# PIC18F25k50-USB_ICSP-Board.net
KiCad netlist of a schematic drawn in EAGLE
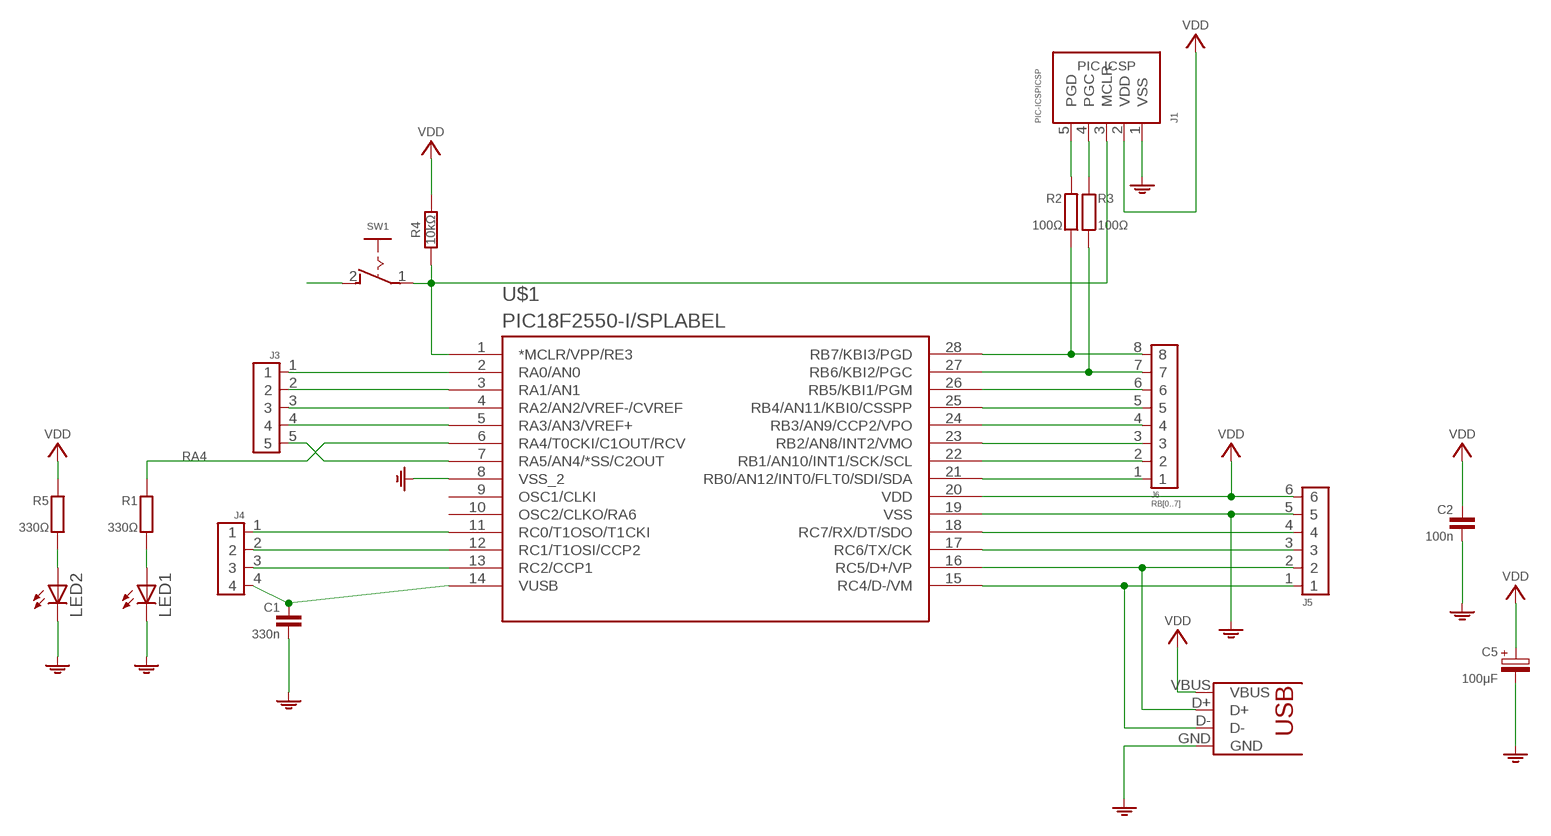
[diagram p0: schematic, sheet 1]

(export (version "E")
  (design (tool "Eeschema 10.0.6"))
  (components
    (comp (ref "C1")
      (value "330n")
      (footprint "eagle-import:C050-030X075")
      (libsource (lib "eagle-import") (part "C050-030X075"))
    )
    (comp (ref "C2")
      (value "100n")
      (footprint "eagle-import:C025-015X024")
      (libsource (lib "eagle-import") (part "C025-015X024"))
    )
    (comp (ref "C5")
      (value "100μF")
      (footprint "eagle-import:E2,5-5")
      (libsource (lib "eagle-import") (part "CPOLE2.5-5"))
    )
    (comp (ref "J1")
      (value "PIC-ICSPICSP")
      (footprint "eagle-import:PIC-ICSP")
      (libsource (lib "eagle-import") (part "PIC-ICSPICSP"))
    )
    (comp (ref "J2")
      (value "USB-PRINT")
      (footprint "eagle-import:USB-B-PRINT")
      (libsource (lib "eagle-import") (part "USB-PRINT"))
    )
    (comp (ref "J3")
      (value "RA[0..4]")
      (footprint "eagle-import:CONN-5P")
      (libsource (lib "eagle-import") (part "CONN-5P-5P"))
    )
    (comp (ref "J4")
      (value "RC[0..3]")
      (footprint "eagle-import:CONN-4P")
      (libsource (lib "eagle-import") (part "CONN-4P-4P"))
    )
    (comp (ref "J5")
      (value "PWR+SCI+USB")
      (footprint "eagle-import:CONN-6P")
      (libsource (lib "eagle-import") (part "CONN-6P"))
    )
    (comp (ref "J6")
      (value "RB[0..7]")
      (footprint "eagle-import:CONN-8P")
      (libsource (lib "eagle-import") (part "CONN-8P"))
    )
    (comp (ref "LED1")
      (value "LED5MM")
      (footprint "eagle-import:LED5MM")
      (libsource (lib "eagle-import") (part "LED5MM"))
    )
    (comp (ref "LED2")
      (value "LED5MM")
      (footprint "eagle-import:LED5MM")
      (libsource (lib "eagle-import") (part "LED5MM"))
    )
    (comp (ref "R1")
      (value "330Ω")
      (footprint "eagle-import:0204_10")
      (libsource (lib "eagle-import") (part "R0204/10"))
    )
    (comp (ref "R2")
      (value "100Ω")
      (footprint "eagle-import:0204_7-V")
      (libsource (lib "eagle-import") (part "R0204/7-V"))
    )
    (comp (ref "R3")
      (value "100Ω")
      (footprint "eagle-import:0204_7-V")
      (libsource (lib "eagle-import") (part "R0204/7-V"))
    )
    (comp (ref "R4")
      (value "10kΩ")
      (footprint "eagle-import:0204_10")
      (libsource (lib "eagle-import") (part "R-H0204/10"))
    )
    (comp (ref "R5")
      (value "330Ω")
      (footprint "eagle-import:0204_10")
      (libsource (lib "eagle-import") (part "R0204/10"))
    )
    (comp (ref "SW1")
      (value "PB-1P-1T")
      (footprint "eagle-import:PB-1P1T")
      (libsource (lib "eagle-import") (part "PB-1P-1T"))
    )
    (comp (ref "U$1")
      (value "PIC18F2550-I/SPLABEL")
      (footprint "eagle-import:PIC18F2550-V")
      (libsource (lib "eagle-import") (part "PIC18F2550-I/SPLABEL"))
    )
  )
  (nets
    (net (code "1") (name "/RA4") (class "Default")
      (node (ref "R1") (pin "1") (pinfunction "2_1") (pintype "passive"))
      (node (ref "U$1") (pin "6") (pinfunction "RA4/T0CKI/C1OUT/RCV_6") (pintype "passive"))
    )
    (net (code "2") (name "GND") (class "Default")
      (node (ref "C1") (pin "2") (pinfunction "2_2") (pintype "passive"))
      (node (ref "C2") (pin "2") (pinfunction "2_2") (pintype "passive"))
      (node (ref "C5") (pin "-") (pinfunction "-_-") (pintype "passive"))
      (node (ref "J1") (pin "1") (pinfunction "VSS_1") (pintype "passive"))
      (node (ref "J2") (pin "GND") (pinfunction "GND_GND") (pintype "bidirectional"))
      (node (ref "J5") (pin "5") (pinfunction "5_5") (pintype "bidirectional"))
      (node (ref "LED1") (pin "K") (pinfunction "C_K") (pintype "passive"))
      (node (ref "LED2") (pin "K") (pinfunction "C_K") (pintype "passive"))
      (node (ref "SW1") (pin "2") (pinfunction "S_2") (pintype "passive"))
      (node (ref "U$1") (pin "19") (pinfunction "VSS_19") (pintype "passive"))
      (node (ref "U$1") (pin "8") (pinfunction "VSS_2_8") (pintype "passive"))
    )
    (net (code "3") (name "Net-(J1-MCLR)") (class "Default")
      (node (ref "J1") (pin "3") (pinfunction "MCLR_3") (pintype "passive"))
      (node (ref "R4") (pin "1") (pinfunction "1_1") (pintype "passive"))
      (node (ref "SW1") (pin "1") (pinfunction "P_1") (pintype "passive"))
      (node (ref "U$1") (pin "1") (pinfunction "*MCLR/VPP/RE3_1") (pintype "passive"))
    )
    (net (code "4") (name "Net-(J1-PGC)") (class "Default")
      (node (ref "J1") (pin "4") (pinfunction "PGC_4") (pintype "passive"))
      (node (ref "R3") (pin "1") (pinfunction "2_1") (pintype "passive"))
    )
    (net (code "5") (name "Net-(J1-PGD)") (class "Default")
      (node (ref "J1") (pin "5") (pinfunction "PGD_5") (pintype "passive"))
      (node (ref "R2") (pin "1") (pinfunction "2_1") (pintype "passive"))
    )
    (net (code "6") (name "Net-(R1-1)") (class "Default")
      (node (ref "LED1") (pin "A") (pinfunction "A_A") (pintype "passive"))
      (node (ref "R1") (pin "2") (pinfunction "1_2") (pintype "passive"))
    )
    (net (code "7") (name "Net-(R2-1)") (class "Default")
      (node (ref "J6") (pin "8") (pinfunction "8_8") (pintype "passive"))
      (node (ref "R2") (pin "2") (pinfunction "1_2") (pintype "passive"))
      (node (ref "U$1") (pin "28") (pinfunction "RB7/KBI3/PGD_28") (pintype "passive"))
    )
    (net (code "8") (name "Net-(R3-1)") (class "Default")
      (node (ref "J6") (pin "7") (pinfunction "7_7") (pintype "passive"))
      (node (ref "R3") (pin "2") (pinfunction "1_2") (pintype "passive"))
      (node (ref "U$1") (pin "27") (pinfunction "RB6/KBI2/PGC_27") (pintype "passive"))
    )
    (net (code "9") (name "Net-(R5-1)") (class "Default")
      (node (ref "LED2") (pin "A") (pinfunction "A_A") (pintype "passive"))
      (node (ref "R5") (pin "2") (pinfunction "1_2") (pintype "passive"))
    )
    (net (code "10") (name "Net-(U$1-RA0{slash}AN0)") (class "Default")
      (node (ref "J3") (pin "1") (pinfunction "1_1") (pintype "bidirectional"))
      (node (ref "U$1") (pin "2") (pinfunction "RA0/AN0_2") (pintype "passive"))
    )
    (net (code "11") (name "Net-(U$1-RA1{slash}AN1)") (class "Default")
      (node (ref "J3") (pin "2") (pinfunction "2_2") (pintype "bidirectional"))
      (node (ref "U$1") (pin "3") (pinfunction "RA1/AN1_3") (pintype "passive"))
    )
    (net (code "12") (name "Net-(U$1-RA2{slash}AN2{slash}VREF-{slash}CVREF)") (class "Default")
      (node (ref "J3") (pin "3") (pinfunction "3_3") (pintype "bidirectional"))
      (node (ref "U$1") (pin "4") (pinfunction "RA2/AN2/VREF-/CVREF_4") (pintype "passive"))
    )
    (net (code "13") (name "Net-(U$1-RA3{slash}AN3{slash}VREF+)") (class "Default")
      (node (ref "J3") (pin "4") (pinfunction "4_4") (pintype "bidirectional"))
      (node (ref "U$1") (pin "5") (pinfunction "RA3/AN3/VREF+_5") (pintype "passive"))
    )
    (net (code "14") (name "Net-(U$1-RA5{slash}AN4{slash}*SS{slash}C2OUT)") (class "Default")
      (node (ref "J3") (pin "5") (pinfunction "5_5") (pintype "bidirectional"))
      (node (ref "U$1") (pin "7") (pinfunction "RA5/AN4/*SS/C2OUT_7") (pintype "passive"))
    )
    (net (code "15") (name "Net-(U$1-RB0{slash}AN12{slash}INT0{slash}FLT0{slash}SDI{slash}SDA)") (class "Default")
      (node (ref "J6") (pin "1") (pinfunction "1_1") (pintype "passive"))
      (node (ref "U$1") (pin "21") (pinfunction "RB0/AN12/INT0/FLT0/SDI/SDA_21") (pintype "passive"))
    )
    (net (code "16") (name "Net-(U$1-RB1{slash}AN10{slash}INT1{slash}SCK{slash}SCL)") (class "Default")
      (node (ref "J6") (pin "2") (pinfunction "2_2") (pintype "passive"))
      (node (ref "U$1") (pin "22") (pinfunction "RB1/AN10/INT1/SCK/SCL_22") (pintype "passive"))
    )
    (net (code "17") (name "Net-(U$1-RB2{slash}AN8{slash}INT2{slash}VMO)") (class "Default")
      (node (ref "J6") (pin "3") (pinfunction "3_3") (pintype "passive"))
      (node (ref "U$1") (pin "23") (pinfunction "RB2/AN8/INT2/VMO_23") (pintype "passive"))
    )
    (net (code "18") (name "Net-(U$1-RB3{slash}AN9{slash}CCP2{slash}VPO)") (class "Default")
      (node (ref "J6") (pin "4") (pinfunction "4_4") (pintype "passive"))
      (node (ref "U$1") (pin "24") (pinfunction "RB3/AN9/CCP2/VPO_24") (pintype "passive"))
    )
    (net (code "19") (name "Net-(U$1-RB4{slash}AN11{slash}KBI0{slash}CSSPP)") (class "Default")
      (node (ref "J6") (pin "5") (pinfunction "5_5") (pintype "passive"))
      (node (ref "U$1") (pin "25") (pinfunction "RB4/AN11/KBI0/CSSPP_25") (pintype "passive"))
    )
    (net (code "20") (name "Net-(U$1-RB5{slash}KBI1{slash}PGM)") (class "Default")
      (node (ref "J6") (pin "6") (pinfunction "6_6") (pintype "passive"))
      (node (ref "U$1") (pin "26") (pinfunction "RB5/KBI1/PGM_26") (pintype "passive"))
    )
    (net (code "21") (name "Net-(U$1-RC0{slash}T1OSO{slash}T1CKI)") (class "Default")
      (node (ref "J4") (pin "1") (pinfunction "1_1") (pintype "bidirectional"))
      (node (ref "U$1") (pin "11") (pinfunction "RC0/T1OSO/T1CKI_11") (pintype "passive"))
    )
    (net (code "22") (name "Net-(U$1-RC1{slash}T1OSI{slash}CCP2)") (class "Default")
      (node (ref "J4") (pin "2") (pinfunction "2_2") (pintype "bidirectional"))
      (node (ref "U$1") (pin "12") (pinfunction "RC1/T1OSI/CCP2_12") (pintype "passive"))
    )
    (net (code "23") (name "Net-(U$1-RC2{slash}CCP1)") (class "Default")
      (node (ref "J4") (pin "3") (pinfunction "3_3") (pintype "bidirectional"))
      (node (ref "U$1") (pin "13") (pinfunction "RC2/CCP1_13") (pintype "passive"))
    )
    (net (code "24") (name "Net-(U$1-RC4{slash}D-{slash}VM)") (class "Default")
      (node (ref "J2") (pin "D-") (pinfunction "D-_D-") (pintype "bidirectional"))
      (node (ref "J5") (pin "1") (pinfunction "1_1") (pintype "bidirectional"))
      (node (ref "U$1") (pin "15") (pinfunction "RC4/D-/VM_15") (pintype "passive"))
    )
    (net (code "25") (name "Net-(U$1-RC5{slash}D+{slash}VP)") (class "Default")
      (node (ref "J2") (pin "D+") (pinfunction "D+_D+") (pintype "bidirectional"))
      (node (ref "J5") (pin "2") (pinfunction "2_2") (pintype "bidirectional"))
      (node (ref "U$1") (pin "16") (pinfunction "RC5/D+/VP_16") (pintype "passive"))
    )
    (net (code "26") (name "Net-(U$1-RC6{slash}TX{slash}CK)") (class "Default")
      (node (ref "J5") (pin "3") (pinfunction "3_3") (pintype "bidirectional"))
      (node (ref "U$1") (pin "17") (pinfunction "RC6/TX/CK_17") (pintype "passive"))
    )
    (net (code "27") (name "Net-(U$1-RC7{slash}RX{slash}DT{slash}SDO)") (class "Default")
      (node (ref "J5") (pin "4") (pinfunction "4_4") (pintype "bidirectional"))
      (node (ref "U$1") (pin "18") (pinfunction "RC7/RX/DT/SDO_18") (pintype "passive"))
    )
    (net (code "28") (name "Net-(U$1-VUSB)") (class "Default")
      (node (ref "C1") (pin "1") (pinfunction "1_1") (pintype "passive"))
      (node (ref "J4") (pin "4") (pinfunction "4_4") (pintype "bidirectional"))
      (node (ref "U$1") (pin "14") (pinfunction "VUSB_14") (pintype "passive"))
    )
    (net (code "29") (name "VDD") (class "Default")
      (node (ref "C2") (pin "1") (pinfunction "1_1") (pintype "passive"))
      (node (ref "C5") (pin "+") (pinfunction "+_+") (pintype "passive"))
      (node (ref "J1") (pin "2") (pinfunction "VDD_2") (pintype "passive"))
      (node (ref "J2") (pin "VBUS") (pinfunction "VBUS_VBUS") (pintype "bidirectional"))
      (node (ref "J5") (pin "6") (pinfunction "6_6") (pintype "bidirectional"))
      (node (ref "R4") (pin "2") (pinfunction "2_2") (pintype "passive"))
      (node (ref "R5") (pin "1") (pinfunction "2_1") (pintype "passive"))
      (node (ref "U$1") (pin "20") (pinfunction "VDD_20") (pintype "passive"))
    )
    (net (code "30") (name "unconnected-(U$1-OSC1{slash}CLKI-Pad9)") (class "Default")
      (node (ref "U$1") (pin "9") (pinfunction "OSC1/CLKI_9") (pintype "passive"))
    )
    (net (code "31") (name "unconnected-(U$1-OSC2{slash}CLKO{slash}RA6-Pad10)") (class "Default")
      (node (ref "U$1") (pin "10") (pinfunction "OSC2/CLKO/RA6_10") (pintype "passive"))
    )
  )
)
